# FlightCPU.net
KiCad netlist of a schematic drawn in EAGLE
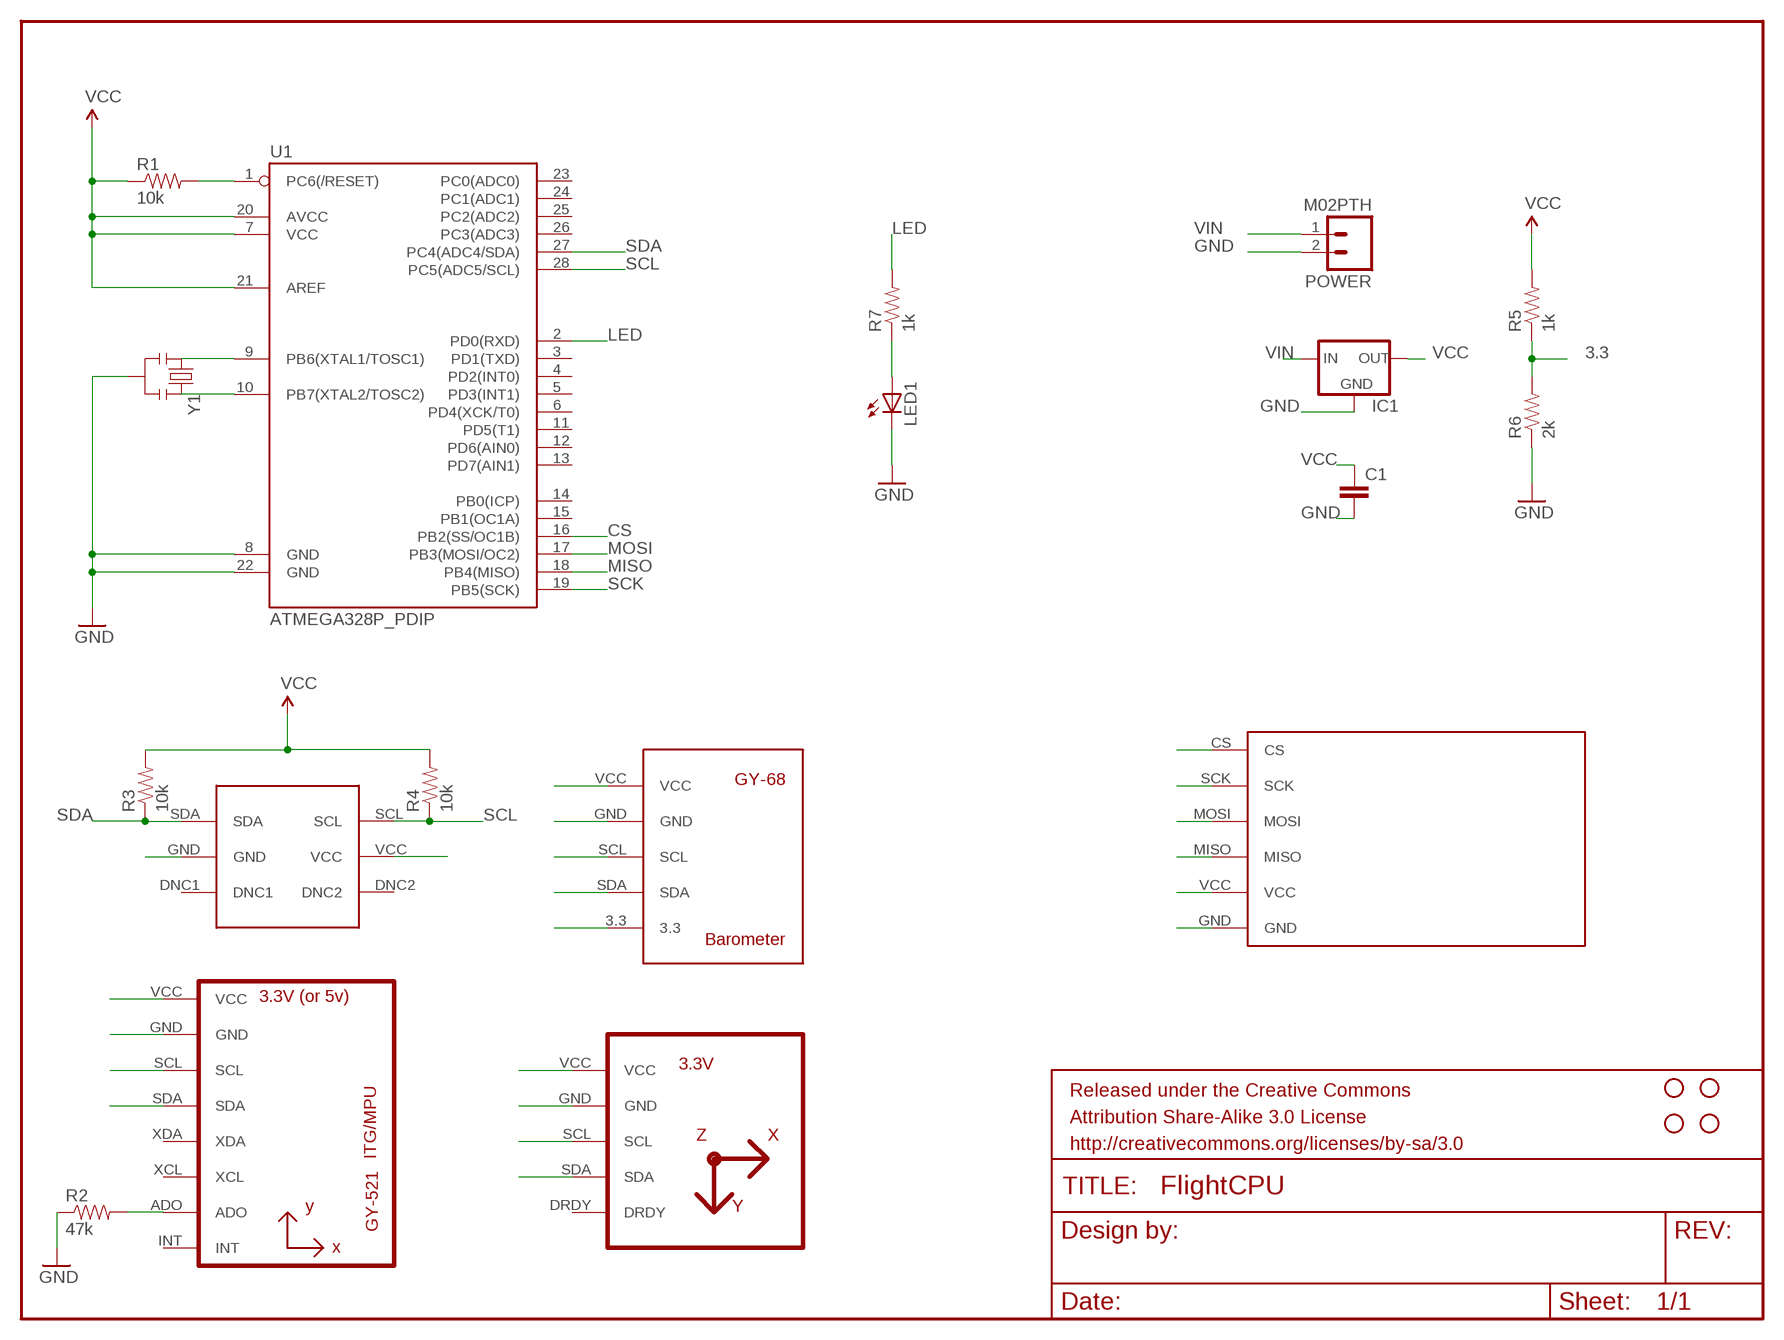
[diagram p0: schematic, sheet 1]

(export (version "E")
  (design (tool "Eeschema 10.0.6"))
  (components
    (comp (ref "C1")
      (value "CAPKIT")
      (footprint "eagle-import:CAP-PTH-SMALL-KIT")
      (libsource (lib "eagle-import") (part "CAPKIT"))
    )
    (comp (ref "FRAME1")
      (value "FRAME-LETTER")
      (footprint "eagle-import:CREATIVE_COMMONS")
      (libsource (lib "eagle-import") (part "FRAME-LETTER"))
    )
    (comp (ref "IC1")
      (value "V_REG_78XXSIDE")
      (footprint "eagle-import:78XXL")
      (libsource (lib "eagle-import") (part "V_REG_78XXSIDE"))
    )
    (comp (ref "LED1")
      (value "LED3MM")
      (footprint "eagle-import:LED3MM")
      (libsource (lib "eagle-import") (part "LED3MM"))
    )
    (comp (ref "POWER")
      (value "M02PTH")
      (footprint "eagle-import:1X02")
      (libsource (lib "eagle-import") (part "M02PTH"))
    )
    (comp (ref "R1")
      (value "10k")
      (footprint "eagle-import:AXIAL-0.3")
      (libsource (lib "eagle-import") (part "RESISTORAXIAL-0.3"))
    )
    (comp (ref "R2")
      (value "47k")
      (footprint "eagle-import:AXIAL-0.3")
      (libsource (lib "eagle-import") (part "RESISTORAXIAL-0.3"))
    )
    (comp (ref "R3")
      (value "10k")
      (footprint "eagle-import:AXIAL-0.3")
      (libsource (lib "eagle-import") (part "RESISTORAXIAL-0.3"))
    )
    (comp (ref "R4")
      (value "10k")
      (footprint "eagle-import:AXIAL-0.3")
      (libsource (lib "eagle-import") (part "RESISTORAXIAL-0.3"))
    )
    (comp (ref "R5")
      (value "1k")
      (footprint "eagle-import:AXIAL-0.3")
      (libsource (lib "eagle-import") (part "RESISTORAXIAL-0.3"))
    )
    (comp (ref "R6")
      (value "2k")
      (footprint "eagle-import:AXIAL-0.3")
      (libsource (lib "eagle-import") (part "RESISTORAXIAL-0.3"))
    )
    (comp (ref "R7")
      (value "1k")
      (footprint "eagle-import:AXIAL-0.3")
      (libsource (lib "eagle-import") (part "RESISTORAXIAL-0.3"))
    )
    (comp (ref "STANDOFF1")
      (value "STAND-OFF")
      (footprint "eagle-import:STAND-OFF")
      (libsource (lib "eagle-import") (part "STAND-OFF"))
    )
    (comp (ref "STANDOFF2")
      (value "STAND-OFF")
      (footprint "eagle-import:STAND-OFF")
      (libsource (lib "eagle-import") (part "STAND-OFF"))
    )
    (comp (ref "STANDOFF3")
      (value "STAND-OFF")
      (footprint "eagle-import:STAND-OFF")
      (libsource (lib "eagle-import") (part "STAND-OFF"))
    )
    (comp (ref "STANDOFF4")
      (value "STAND-OFF")
      (footprint "eagle-import:STAND-OFF")
      (libsource (lib "eagle-import") (part "STAND-OFF"))
    )
    (comp (ref "U$1")
      (value "SI7020_DIP")
      (footprint "eagle-import:SI7020")
      (libsource (lib "eagle-import") (part "SI7020_DIP"))
    )
    (comp (ref "U$2")
      (value "GY-68")
      (footprint "eagle-import:GY-68")
      (libsource (lib "eagle-import") (part "GY-68"))
    )
    (comp (ref "U$3")
      (value "MICRO_SD")
      (footprint "eagle-import:MICROSD")
      (libsource (lib "eagle-import") (part "MICRO_SD"))
    )
    (comp (ref "U1")
      (value "ATMEGA328P_PDIP")
      (footprint "eagle-import:DIL28-3")
      (libsource (lib "eagle-import") (part "ATMEGA328P_PDIP"))
    )
    (comp (ref "U2")
      (value "GY-521MPU6050")
      (footprint "eagle-import:GY-521")
      (libsource (lib "eagle-import") (part "GY-521MPU6050"))
    )
    (comp (ref "U3")
      (value "HMC5883LGY-271")
      (footprint "eagle-import:GY-271")
      (libsource (lib "eagle-import") (part "HMC5883LGY-271"))
    )
    (comp (ref "Y1")
      (value "RESONATORPTH")
      (footprint "eagle-import:RESONATOR-PTH")
      (libsource (lib "eagle-import") (part "RESONATORPTH"))
    )
  )
  (nets
    (net (code "1") (name "/3.3") (class "Default")
      (node (ref "R5") (pin "P$1") (pinfunction "1_P$1") (pintype "passive"))
      (node (ref "R6") (pin "P$2") (pinfunction "2_P$2") (pintype "passive"))
      (node (ref "U$2") (pin "3.3") (pinfunction "3.3_3.3") (pintype "bidirectional"))
    )
    (net (code "2") (name "/CS") (class "Default")
      (node (ref "U$3") (pin "CS") (pinfunction "CS_CS") (pintype "bidirectional"))
      (node (ref "U1") (pin "16") (pinfunction "PB2(SS/OC1B)_16") (pintype "bidirectional"))
    )
    (net (code "3") (name "/LED") (class "Default")
      (node (ref "R7") (pin "P$2") (pinfunction "2_P$2") (pintype "passive"))
      (node (ref "U1") (pin "2") (pinfunction "PD0(RXD)_2") (pintype "bidirectional"))
    )
    (net (code "4") (name "/MISO") (class "Default")
      (node (ref "U$3") (pin "MISO") (pinfunction "MISO_MISO") (pintype "bidirectional"))
      (node (ref "U1") (pin "18") (pinfunction "PB4(MISO)_18") (pintype "bidirectional"))
    )
    (net (code "5") (name "/MOSI") (class "Default")
      (node (ref "U$3") (pin "MOSI") (pinfunction "MOSI_MOSI") (pintype "bidirectional"))
      (node (ref "U1") (pin "17") (pinfunction "PB3(MOSI/OC2)_17") (pintype "bidirectional"))
    )
    (net (code "6") (name "/SCK") (class "Default")
      (node (ref "U$3") (pin "SCK") (pinfunction "SCK_SCK") (pintype "bidirectional"))
      (node (ref "U1") (pin "19") (pinfunction "PB5(SCK)_19") (pintype "bidirectional"))
    )
    (net (code "7") (name "/SCL") (class "Default")
      (node (ref "R4") (pin "P$1") (pinfunction "1_P$1") (pintype "passive"))
      (node (ref "U$1") (pin "SCL") (pinfunction "SCL_SCL") (pintype "bidirectional"))
      (node (ref "U$2") (pin "SCL") (pinfunction "SCL_SCL") (pintype "bidirectional"))
      (node (ref "U1") (pin "28") (pinfunction "PC5(ADC5/SCL)_28") (pintype "bidirectional"))
      (node (ref "U2") (pin "SCL") (pinfunction "SCL_SCL") (pintype "bidirectional"))
      (node (ref "U3") (pin "SCL") (pinfunction "SCL_SCL") (pintype "bidirectional"))
    )
    (net (code "8") (name "/SDA") (class "Default")
      (node (ref "R3") (pin "P$1") (pinfunction "1_P$1") (pintype "passive"))
      (node (ref "U$1") (pin "SDA") (pinfunction "SDA_SDA") (pintype "bidirectional"))
      (node (ref "U$2") (pin "SDA") (pinfunction "SDA_SDA") (pintype "bidirectional"))
      (node (ref "U1") (pin "27") (pinfunction "PC4(ADC4/SDA)_27") (pintype "bidirectional"))
      (node (ref "U2") (pin "SDA") (pinfunction "SDA_SDA") (pintype "bidirectional"))
      (node (ref "U3") (pin "SDA") (pinfunction "SDA_SDA") (pintype "bidirectional"))
    )
    (net (code "9") (name "/VIN") (class "Default")
      (node (ref "IC1") (pin "IN") (pinfunction "IN_IN") (pintype "input"))
      (node (ref "POWER") (pin "1") (pinfunction "1_1") (pintype "passive"))
    )
    (net (code "10") (name "GND") (class "Default")
      (node (ref "C1") (pin "2") (pinfunction "2_2") (pintype "passive"))
      (node (ref "IC1") (pin "GND") (pinfunction "GND_GND") (pintype "input"))
      (node (ref "LED1") (pin "K") (pinfunction "C_K") (pintype "passive"))
      (node (ref "POWER") (pin "2") (pinfunction "2_2") (pintype "passive"))
      (node (ref "R2") (pin "P$1") (pinfunction "1_P$1") (pintype "passive"))
      (node (ref "R6") (pin "P$1") (pinfunction "1_P$1") (pintype "passive"))
      (node (ref "U$1") (pin "GND") (pinfunction "GND_GND") (pintype "bidirectional"))
      (node (ref "U$2") (pin "GND") (pinfunction "GND_GND") (pintype "bidirectional"))
      (node (ref "U$3") (pin "GND") (pinfunction "GND_GND") (pintype "bidirectional"))
      (node (ref "U1") (pin "22") (pinfunction "GND_22") (pintype "bidirectional"))
      (node (ref "U1") (pin "8") (pinfunction "GND_8") (pintype "bidirectional"))
      (node (ref "U2") (pin "GND") (pinfunction "GND_GND") (pintype "bidirectional"))
      (node (ref "U3") (pin "GND") (pinfunction "GND_GND") (pintype "bidirectional"))
      (node (ref "Y1") (pin "2") (pinfunction "2_2") (pintype "passive"))
    )
    (net (code "11") (name "Net-(R1-2)") (class "Default")
      (node (ref "R1") (pin "P$2") (pinfunction "2_P$2") (pintype "passive"))
      (node (ref "U1") (pin "1") (pinfunction "PC6(/RESET)_1") (pintype "bidirectional"))
    )
    (net (code "12") (name "Net-(R2-2)") (class "Default")
      (node (ref "R2") (pin "P$2") (pinfunction "2_P$2") (pintype "passive"))
      (node (ref "U2") (pin "ADO") (pinfunction "ADO_ADO") (pintype "bidirectional"))
    )
    (net (code "13") (name "Net-(R7-1)") (class "Default")
      (node (ref "LED1") (pin "A") (pinfunction "A_A") (pintype "passive"))
      (node (ref "R7") (pin "P$1") (pinfunction "1_P$1") (pintype "passive"))
    )
    (net (code "14") (name "Net-(U1-PB6(XTAL1{slash}TOSC1))") (class "Default")
      (node (ref "U1") (pin "9") (pinfunction "PB6(XTAL1/TOSC1)_9") (pintype "bidirectional"))
      (node (ref "Y1") (pin "1") (pinfunction "1_1") (pintype "passive"))
    )
    (net (code "15") (name "Net-(U1-PB7(XTAL2{slash}TOSC2))") (class "Default")
      (node (ref "U1") (pin "10") (pinfunction "PB7(XTAL2/TOSC2)_10") (pintype "bidirectional"))
      (node (ref "Y1") (pin "3") (pinfunction "3_3") (pintype "passive"))
    )
    (net (code "16") (name "VCC") (class "Default")
      (node (ref "C1") (pin "1") (pinfunction "1_1") (pintype "passive"))
      (node (ref "IC1") (pin "OUT") (pinfunction "OUT_OUT") (pintype "output"))
      (node (ref "R1") (pin "P$1") (pinfunction "1_P$1") (pintype "passive"))
      (node (ref "R3") (pin "P$2") (pinfunction "2_P$2") (pintype "passive"))
      (node (ref "R4") (pin "P$2") (pinfunction "2_P$2") (pintype "passive"))
      (node (ref "R5") (pin "P$2") (pinfunction "2_P$2") (pintype "passive"))
      (node (ref "U$1") (pin "VCC") (pinfunction "VCC_VCC") (pintype "bidirectional"))
      (node (ref "U$2") (pin "VCC") (pinfunction "VCC_VCC") (pintype "bidirectional"))
      (node (ref "U$3") (pin "VCC") (pinfunction "VCC_VCC") (pintype "bidirectional"))
      (node (ref "U1") (pin "20") (pinfunction "AVCC_20") (pintype "bidirectional"))
      (node (ref "U1") (pin "21") (pinfunction "AREF_21") (pintype "bidirectional"))
      (node (ref "U1") (pin "7") (pinfunction "VCC_7") (pintype "bidirectional"))
      (node (ref "U2") (pin "VCC") (pinfunction "VCC_VCC") (pintype "bidirectional"))
      (node (ref "U3") (pin "VCC") (pinfunction "VCC_VCC") (pintype "bidirectional"))
    )
    (net (code "17") (name "unconnected-(U$1-PadDNC1)") (class "Default")
      (node (ref "U$1") (pin "DNC1") (pinfunction "DNC1_DNC1") (pintype "bidirectional"))
    )
    (net (code "18") (name "unconnected-(U$1-PadDNC2)") (class "Default")
      (node (ref "U$1") (pin "DNC2") (pinfunction "DNC2_DNC2") (pintype "bidirectional"))
    )
    (net (code "19") (name "unconnected-(U1-PB0(ICP)-Pad14)") (class "Default")
      (node (ref "U1") (pin "14") (pinfunction "PB0(ICP)_14") (pintype "bidirectional"))
    )
    (net (code "20") (name "unconnected-(U1-PB1(OC1A)-Pad15)") (class "Default")
      (node (ref "U1") (pin "15") (pinfunction "PB1(OC1A)_15") (pintype "bidirectional"))
    )
    (net (code "21") (name "unconnected-(U1-PC0(ADC0)-Pad23)") (class "Default")
      (node (ref "U1") (pin "23") (pinfunction "PC0(ADC0)_23") (pintype "bidirectional"))
    )
    (net (code "22") (name "unconnected-(U1-PC1(ADC1)-Pad24)") (class "Default")
      (node (ref "U1") (pin "24") (pinfunction "PC1(ADC1)_24") (pintype "bidirectional"))
    )
    (net (code "23") (name "unconnected-(U1-PC2(ADC2)-Pad25)") (class "Default")
      (node (ref "U1") (pin "25") (pinfunction "PC2(ADC2)_25") (pintype "bidirectional"))
    )
    (net (code "24") (name "unconnected-(U1-PC3(ADC3)-Pad26)") (class "Default")
      (node (ref "U1") (pin "26") (pinfunction "PC3(ADC3)_26") (pintype "bidirectional"))
    )
    (net (code "25") (name "unconnected-(U1-PD1(TXD)-Pad3)") (class "Default")
      (node (ref "U1") (pin "3") (pinfunction "PD1(TXD)_3") (pintype "bidirectional"))
    )
    (net (code "26") (name "unconnected-(U1-PD2(INT0)-Pad4)") (class "Default")
      (node (ref "U1") (pin "4") (pinfunction "PD2(INT0)_4") (pintype "bidirectional"))
    )
    (net (code "27") (name "unconnected-(U1-PD3(INT1)-Pad5)") (class "Default")
      (node (ref "U1") (pin "5") (pinfunction "PD3(INT1)_5") (pintype "bidirectional"))
    )
    (net (code "28") (name "unconnected-(U1-PD4(XCK{slash}T0)-Pad6)") (class "Default")
      (node (ref "U1") (pin "6") (pinfunction "PD4(XCK/T0)_6") (pintype "bidirectional"))
    )
    (net (code "29") (name "unconnected-(U1-PD5(T1)-Pad11)") (class "Default")
      (node (ref "U1") (pin "11") (pinfunction "PD5(T1)_11") (pintype "bidirectional"))
    )
    (net (code "30") (name "unconnected-(U1-PD6(AIN0)-Pad12)") (class "Default")
      (node (ref "U1") (pin "12") (pinfunction "PD6(AIN0)_12") (pintype "bidirectional"))
    )
    (net (code "31") (name "unconnected-(U1-PD7(AIN1)-Pad13)") (class "Default")
      (node (ref "U1") (pin "13") (pinfunction "PD7(AIN1)_13") (pintype "bidirectional"))
    )
    (net (code "32") (name "unconnected-(U2-PadINT)") (class "Default")
      (node (ref "U2") (pin "INT") (pinfunction "INT_INT") (pintype "bidirectional"))
    )
    (net (code "33") (name "unconnected-(U2-PadXCL)") (class "Default")
      (node (ref "U2") (pin "XCL") (pinfunction "XCL_XCL") (pintype "bidirectional"))
    )
    (net (code "34") (name "unconnected-(U2-PadXDA)") (class "Default")
      (node (ref "U2") (pin "XDA") (pinfunction "XDA_XDA") (pintype "bidirectional"))
    )
    (net (code "35") (name "unconnected-(U3-PadDRDY)") (class "Default")
      (node (ref "U3") (pin "DRDY") (pinfunction "DRDY_DRDY") (pintype "bidirectional"))
    )
  )
)
